# SystemMemory.net
KiCad netlist of a schematic drawn in Altium Designer
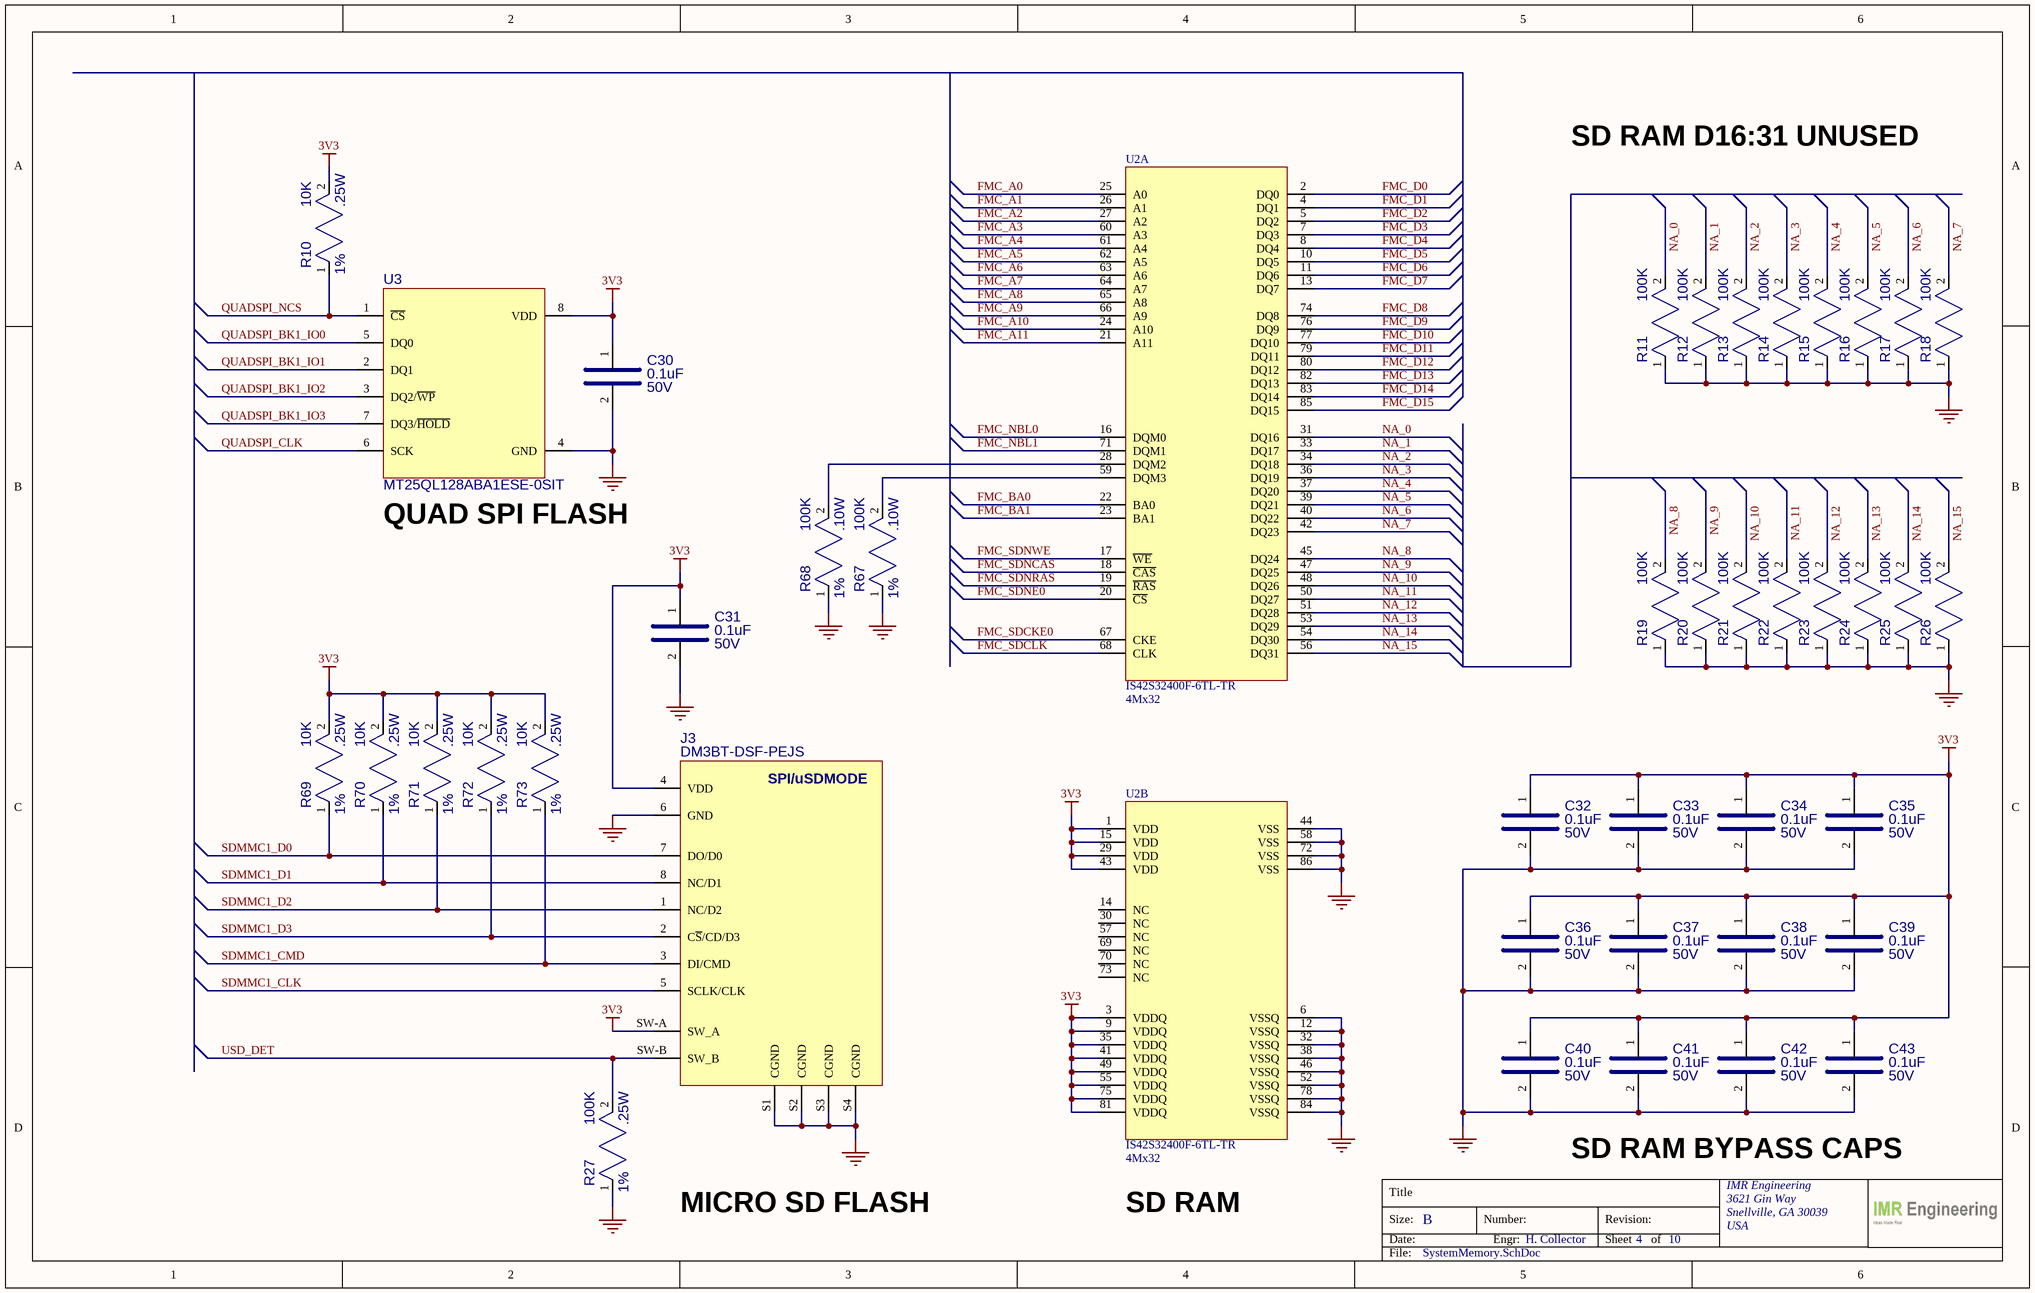
[diagram p0: SystemMemory.SchDoc]

(export (version "E")
  (design (tool "Eeschema 10.0.6"))
  (components
    (comp (ref "C30")
      (value "0.1uF")
      (footprint "CAP_0805")
      (description "CAP CER 0.1UF 50V X7R 0805")
      (fields (field (name "MFG") "AVX") (field (name "TOLERANCE") "10%") (field (name "VOLTAGE") "50V"))
      (libsource (lib "IMR_Lib") (part "CAP_0.1UF_50V_0805"))
    )
    (comp (ref "C31")
      (value "0.1uF")
      (footprint "CAP_0805")
      (description "CAP CER 0.1UF 50V X7R 0805")
      (fields (field (name "MFG") "AVX") (field (name "TOLERANCE") "10%") (field (name "VOLTAGE") "50V"))
      (libsource (lib "IMR_Lib") (part "CAP_0.1UF_50V_0805"))
    )
    (comp (ref "C32")
      (value "0.1uF")
      (footprint "CAP_0603")
      (description "CAP CER 0.1UF 50V X7R 0603")
      (fields (field (name "MFG") "Yageo") (field (name "TOLERANCE") "10%") (field (name "VOLTAGE") "50V"))
      (libsource (lib "IMR_Lib") (part "CAP_0.1UF_50V_0603"))
    )
    (comp (ref "C33")
      (value "0.1uF")
      (footprint "CAP_0603")
      (description "CAP CER 0.1UF 50V X7R 0603")
      (fields (field (name "MFG") "Yageo") (field (name "TOLERANCE") "10%") (field (name "VOLTAGE") "50V"))
      (libsource (lib "IMR_Lib") (part "CAP_0.1UF_50V_0603"))
    )
    (comp (ref "C34")
      (value "0.1uF")
      (footprint "CAP_0603")
      (description "CAP CER 0.1UF 50V X7R 0603")
      (fields (field (name "MFG") "Yageo") (field (name "TOLERANCE") "10%") (field (name "VOLTAGE") "50V"))
      (libsource (lib "IMR_Lib") (part "CAP_0.1UF_50V_0603"))
    )
    (comp (ref "C35")
      (value "0.1uF")
      (footprint "CAP_0603")
      (description "CAP CER 0.1UF 50V X7R 0603")
      (fields (field (name "MFG") "Yageo") (field (name "TOLERANCE") "10%") (field (name "VOLTAGE") "50V"))
      (libsource (lib "IMR_Lib") (part "CAP_0.1UF_50V_0603"))
    )
    (comp (ref "C36")
      (value "0.1uF")
      (footprint "CAP_0603")
      (description "CAP CER 0.1UF 50V X7R 0603")
      (fields (field (name "MFG") "Yageo") (field (name "TOLERANCE") "10%") (field (name "VOLTAGE") "50V"))
      (libsource (lib "IMR_Lib") (part "CAP_0.1UF_50V_0603"))
    )
    (comp (ref "C37")
      (value "0.1uF")
      (footprint "CAP_0603")
      (description "CAP CER 0.1UF 50V X7R 0603")
      (fields (field (name "MFG") "Yageo") (field (name "TOLERANCE") "10%") (field (name "VOLTAGE") "50V"))
      (libsource (lib "IMR_Lib") (part "CAP_0.1UF_50V_0603"))
    )
    (comp (ref "C38")
      (value "0.1uF")
      (footprint "CAP_0603")
      (description "CAP CER 0.1UF 50V X7R 0603")
      (fields (field (name "MFG") "Yageo") (field (name "TOLERANCE") "10%") (field (name "VOLTAGE") "50V"))
      (libsource (lib "IMR_Lib") (part "CAP_0.1UF_50V_0603"))
    )
    (comp (ref "C39")
      (value "0.1uF")
      (footprint "CAP_0603")
      (description "CAP CER 0.1UF 50V X7R 0603")
      (fields (field (name "MFG") "Yageo") (field (name "TOLERANCE") "10%") (field (name "VOLTAGE") "50V"))
      (libsource (lib "IMR_Lib") (part "CAP_0.1UF_50V_0603"))
    )
    (comp (ref "C40")
      (value "0.1uF")
      (footprint "CAP_0603")
      (description "CAP CER 0.1UF 50V X7R 0603")
      (fields (field (name "MFG") "Yageo") (field (name "TOLERANCE") "10%") (field (name "VOLTAGE") "50V"))
      (libsource (lib "IMR_Lib") (part "CAP_0.1UF_50V_0603"))
    )
    (comp (ref "C41")
      (value "0.1uF")
      (footprint "CAP_0603")
      (description "CAP CER 0.1UF 50V X7R 0603")
      (fields (field (name "MFG") "Yageo") (field (name "TOLERANCE") "10%") (field (name "VOLTAGE") "50V"))
      (libsource (lib "IMR_Lib") (part "CAP_0.1UF_50V_0603"))
    )
    (comp (ref "C42")
      (value "0.1uF")
      (footprint "CAP_0603")
      (description "CAP CER 0.1UF 50V X7R 0603")
      (fields (field (name "MFG") "Yageo") (field (name "TOLERANCE") "10%") (field (name "VOLTAGE") "50V"))
      (libsource (lib "IMR_Lib") (part "CAP_0.1UF_50V_0603"))
    )
    (comp (ref "C43")
      (value "0.1uF")
      (footprint "CAP_0603")
      (description "CAP CER 0.1UF 50V X7R 0603")
      (fields (field (name "MFG") "Yageo") (field (name "TOLERANCE") "10%") (field (name "VOLTAGE") "50V"))
      (libsource (lib "IMR_Lib") (part "CAP_0.1UF_50V_0603"))
    )
    (comp (ref "J3")
      (value "DM3BT-DSF-PEJS")
      (footprint "HRS_DM3BT-DSF-PEJS")
      (description "CONN MICRO SD CARD PUSH-PUSH R/A")
      (fields (field (name "MFG") "Hirose Electric Co Ltd"))
      (libsource (lib "IMR_Lib") (part "CONN_HIROSE_DM3BT-DSF-PEJS"))
    )
    (comp (ref "R10")
      (value "10K")
      (footprint "RES_0805")
      (description "RES SMD 10K OHM 1% 1/4W 0805")
      (fields
        (field (name "MFG") "KOA Speer Electronics, Inc.")
        (field (name "TOLERANCE") "1%")
        (field (name "POWER") ".25W")
        (field (name "Comment") "SG73S2ATTD1002F")
      )
      (libsource (lib "IMR_Lib") (part "RES_10K_0805_1/4W_1%"))
    )
    (comp (ref "R11")
      (value "100K")
      (footprint "RES_0603")
      (description "RES SMD 100K OHM 1% 1/10W 0603")
      (fields (field (name "MFG") "Yageo") (field (name "TOLERANCE") "1%"))
      (libsource (lib "IMR_Lib") (part "RES_100K_0603_1/10W_1%"))
    )
    (comp (ref "R12")
      (value "100K")
      (footprint "RES_0603")
      (description "RES SMD 100K OHM 1% 1/10W 0603")
      (fields (field (name "MFG") "Yageo") (field (name "TOLERANCE") "1%"))
      (libsource (lib "IMR_Lib") (part "RES_100K_0603_1/10W_1%"))
    )
    (comp (ref "R13")
      (value "100K")
      (footprint "RES_0603")
      (description "RES SMD 100K OHM 1% 1/10W 0603")
      (fields (field (name "MFG") "Yageo") (field (name "TOLERANCE") "1%"))
      (libsource (lib "IMR_Lib") (part "RES_100K_0603_1/10W_1%"))
    )
    (comp (ref "R14")
      (value "100K")
      (footprint "RES_0603")
      (description "RES SMD 100K OHM 1% 1/10W 0603")
      (fields (field (name "MFG") "Yageo") (field (name "TOLERANCE") "1%"))
      (libsource (lib "IMR_Lib") (part "RES_100K_0603_1/10W_1%"))
    )
    (comp (ref "R15")
      (value "100K")
      (footprint "RES_0603")
      (description "RES SMD 100K OHM 1% 1/10W 0603")
      (fields (field (name "MFG") "Yageo") (field (name "TOLERANCE") "1%"))
      (libsource (lib "IMR_Lib") (part "RES_100K_0603_1/10W_1%"))
    )
    (comp (ref "R16")
      (value "100K")
      (footprint "RES_0603")
      (description "RES SMD 100K OHM 1% 1/10W 0603")
      (fields (field (name "MFG") "Yageo") (field (name "TOLERANCE") "1%"))
      (libsource (lib "IMR_Lib") (part "RES_100K_0603_1/10W_1%"))
    )
    (comp (ref "R17")
      (value "100K")
      (footprint "RES_0603")
      (description "RES SMD 100K OHM 1% 1/10W 0603")
      (fields (field (name "MFG") "Yageo") (field (name "TOLERANCE") "1%"))
      (libsource (lib "IMR_Lib") (part "RES_100K_0603_1/10W_1%"))
    )
    (comp (ref "R18")
      (value "100K")
      (footprint "RES_0603")
      (description "RES SMD 100K OHM 1% 1/10W 0603")
      (fields (field (name "MFG") "Yageo") (field (name "TOLERANCE") "1%"))
      (libsource (lib "IMR_Lib") (part "RES_100K_0603_1/10W_1%"))
    )
    (comp (ref "R19")
      (value "100K")
      (footprint "RES_0603")
      (description "RES SMD 100K OHM 1% 1/10W 0603")
      (fields (field (name "MFG") "Yageo") (field (name "TOLERANCE") "1%"))
      (libsource (lib "IMR_Lib") (part "RES_100K_0603_1/10W_1%"))
    )
    (comp (ref "R20")
      (value "100K")
      (footprint "RES_0603")
      (description "RES SMD 100K OHM 1% 1/10W 0603")
      (fields (field (name "MFG") "Yageo") (field (name "TOLERANCE") "1%"))
      (libsource (lib "IMR_Lib") (part "RES_100K_0603_1/10W_1%"))
    )
    (comp (ref "R21")
      (value "100K")
      (footprint "RES_0603")
      (description "RES SMD 100K OHM 1% 1/10W 0603")
      (fields (field (name "MFG") "Yageo") (field (name "TOLERANCE") "1%"))
      (libsource (lib "IMR_Lib") (part "RES_100K_0603_1/10W_1%"))
    )
    (comp (ref "R22")
      (value "100K")
      (footprint "RES_0603")
      (description "RES SMD 100K OHM 1% 1/10W 0603")
      (fields (field (name "MFG") "Yageo") (field (name "TOLERANCE") "1%"))
      (libsource (lib "IMR_Lib") (part "RES_100K_0603_1/10W_1%"))
    )
    (comp (ref "R23")
      (value "100K")
      (footprint "RES_0603")
      (description "RES SMD 100K OHM 1% 1/10W 0603")
      (fields (field (name "MFG") "Yageo") (field (name "TOLERANCE") "1%"))
      (libsource (lib "IMR_Lib") (part "RES_100K_0603_1/10W_1%"))
    )
    (comp (ref "R24")
      (value "100K")
      (footprint "RES_0603")
      (description "RES SMD 100K OHM 1% 1/10W 0603")
      (fields (field (name "MFG") "Yageo") (field (name "TOLERANCE") "1%"))
      (libsource (lib "IMR_Lib") (part "RES_100K_0603_1/10W_1%"))
    )
    (comp (ref "R25")
      (value "100K")
      (footprint "RES_0603")
      (description "RES SMD 100K OHM 1% 1/10W 0603")
      (fields (field (name "MFG") "Yageo") (field (name "TOLERANCE") "1%"))
      (libsource (lib "IMR_Lib") (part "RES_100K_0603_1/10W_1%"))
    )
    (comp (ref "R26")
      (value "100K")
      (footprint "RES_0603")
      (description "RES SMD 100K OHM 1% 1/10W 0603")
      (fields (field (name "MFG") "Yageo") (field (name "TOLERANCE") "1%"))
      (libsource (lib "IMR_Lib") (part "RES_100K_0603_1/10W_1%"))
    )
    (comp (ref "R27")
      (value "100K")
      (footprint "PMG_RES_0805")
      (description "RES SMD 100K OHM 1% 1/4W 0805")
      (fields
        (field (name "MFG") "KOA Speer Electronics, Inc.")
        (field (name "TOLERANCE") "1%")
        (field (name "POWER") ".25W")
        (field (name "Comment") "RK73H2ATTD1003F")
      )
      (libsource (lib "IMR_Lib") (part "RES_100K_0805_1/4W_1%"))
    )
    (comp (ref "R67")
      (value "100K")
      (footprint "RES_0603")
      (description "RES SMD 100K OHM 1% 1/10W 0603")
      (fields
        (field (name "MFG") "Yageo")
        (field (name "TOLERANCE") "1%")
        (field (name "POWER") ".10W")
        (field (name "Comment") "RC0603FR-07100KL")
      )
      (libsource (lib "IMR_Lib") (part "RES_100K_0603_1/10W_1%"))
    )
    (comp (ref "R68")
      (value "100K")
      (footprint "RES_0603")
      (description "RES SMD 100K OHM 1% 1/10W 0603")
      (fields
        (field (name "MFG") "Yageo")
        (field (name "TOLERANCE") "1%")
        (field (name "POWER") ".10W")
        (field (name "Comment") "RC0603FR-07100KL")
      )
      (libsource (lib "IMR_Lib") (part "RES_100K_0603_1/10W_1%"))
    )
    (comp (ref "R69")
      (value "10K")
      (footprint "RES_0805")
      (description "RES SMD 10K OHM 1% 1/4W 0805")
      (fields
        (field (name "MFG") "KOA Speer Electronics, Inc.")
        (field (name "TOLERANCE") "1%")
        (field (name "POWER") ".25W")
        (field (name "Comment") "SG73S2ATTD1002F")
      )
      (libsource (lib "IMR_Lib") (part "RES_10K_0805_1/4W_1%"))
    )
    (comp (ref "R70")
      (value "10K")
      (footprint "RES_0805")
      (description "RES SMD 10K OHM 1% 1/4W 0805")
      (fields
        (field (name "MFG") "KOA Speer Electronics, Inc.")
        (field (name "TOLERANCE") "1%")
        (field (name "POWER") ".25W")
        (field (name "Comment") "SG73S2ATTD1002F")
      )
      (libsource (lib "IMR_Lib") (part "RES_10K_0805_1/4W_1%"))
    )
    (comp (ref "R71")
      (value "10K")
      (footprint "RES_0805")
      (description "RES SMD 10K OHM 1% 1/4W 0805")
      (fields
        (field (name "MFG") "KOA Speer Electronics, Inc.")
        (field (name "TOLERANCE") "1%")
        (field (name "POWER") ".25W")
        (field (name "Comment") "SG73S2ATTD1002F")
      )
      (libsource (lib "IMR_Lib") (part "RES_10K_0805_1/4W_1%"))
    )
    (comp (ref "R72")
      (value "10K")
      (footprint "RES_0805")
      (description "RES SMD 10K OHM 1% 1/4W 0805")
      (fields
        (field (name "MFG") "KOA Speer Electronics, Inc.")
        (field (name "TOLERANCE") "1%")
        (field (name "POWER") ".25W")
        (field (name "Comment") "SG73S2ATTD1002F")
      )
      (libsource (lib "IMR_Lib") (part "RES_10K_0805_1/4W_1%"))
    )
    (comp (ref "R73")
      (value "10K")
      (footprint "RES_0805")
      (description "RES SMD 10K OHM 1% 1/4W 0805")
      (fields
        (field (name "MFG") "KOA Speer Electronics, Inc.")
        (field (name "TOLERANCE") "1%")
        (field (name "POWER") ".25W")
        (field (name "Comment") "SG73S2ATTD1002F")
      )
      (libsource (lib "IMR_Lib") (part "RES_10K_0805_1/4W_1%"))
    )
    (comp (ref "U2")
      (value "IS42S32400F-6TL-TR")
      (footprint "86TSOPII")
      (description "IC DRAM 128M PARALLEL 86TSOP II")
      (fields
        (field (name "MFG") "ISSI, Integrated Silicon Solution Inc")
        (field (name "ALTIUM_VALUE") "4Mx32")
      )
      (libsource (lib "IMR_Lib") (part "IC_ IS42S32400F-6TL"))
    )
    (comp (ref "U3")
      (value "MT25QL128ABA1ESE-0SIT")
      (footprint "SO8W")
      (description "IC FLASH 128M SPI 133MHZ 8SOP2")
      (fields (field (name "MFG") "Micron Technology Inc."))
      (libsource (lib "IMR_Lib") (part "IC_MT25QL128ABA1ESE-0SIT"))
    )
  )
  (nets
    (net (code "1") (name "/FMC_A0") (class "Default")
      (node (ref "U2") (pin "25") (pinfunction "A0_25") (pintype "passive"))
    )
    (net (code "2") (name "/FMC_A1") (class "Default")
      (node (ref "U2") (pin "26") (pinfunction "A1_26") (pintype "passive"))
    )
    (net (code "3") (name "/FMC_A2") (class "Default")
      (node (ref "U2") (pin "27") (pinfunction "A2_27") (pintype "passive"))
    )
    (net (code "4") (name "/FMC_A3") (class "Default")
      (node (ref "U2") (pin "60") (pinfunction "A3_60") (pintype "passive"))
    )
    (net (code "5") (name "/FMC_A4") (class "Default")
      (node (ref "U2") (pin "61") (pinfunction "A4_61") (pintype "passive"))
    )
    (net (code "6") (name "/FMC_A5") (class "Default")
      (node (ref "U2") (pin "62") (pinfunction "A5_62") (pintype "passive"))
    )
    (net (code "7") (name "/FMC_A6") (class "Default")
      (node (ref "U2") (pin "63") (pinfunction "A6_63") (pintype "passive"))
    )
    (net (code "8") (name "/FMC_A7") (class "Default")
      (node (ref "U2") (pin "64") (pinfunction "A7_64") (pintype "passive"))
    )
    (net (code "9") (name "/FMC_A8") (class "Default")
      (node (ref "U2") (pin "65") (pinfunction "A8_65") (pintype "passive"))
    )
    (net (code "10") (name "/FMC_A9") (class "Default")
      (node (ref "U2") (pin "66") (pinfunction "A9_66") (pintype "passive"))
    )
    (net (code "11") (name "/FMC_A10") (class "Default")
      (node (ref "U2") (pin "24") (pinfunction "A10_24") (pintype "passive"))
    )
    (net (code "12") (name "/FMC_A11") (class "Default")
      (node (ref "U2") (pin "21") (pinfunction "A11_21") (pintype "passive"))
    )
    (net (code "13") (name "/FMC_BA0") (class "Default")
      (node (ref "U2") (pin "22") (pinfunction "BA0_22") (pintype "passive"))
    )
    (net (code "14") (name "/FMC_BA1") (class "Default")
      (node (ref "U2") (pin "23") (pinfunction "BA1_23") (pintype "passive"))
    )
    (net (code "15") (name "/FMC_D0") (class "Default")
      (node (ref "U2") (pin "2") (pinfunction "DQ0_2") (pintype "passive"))
    )
    (net (code "16") (name "/FMC_D1") (class "Default")
      (node (ref "U2") (pin "4") (pinfunction "DQ1_4") (pintype "passive"))
    )
    (net (code "17") (name "/FMC_D2") (class "Default")
      (node (ref "U2") (pin "5") (pinfunction "DQ2_5") (pintype "passive"))
    )
    (net (code "18") (name "/FMC_D3") (class "Default")
      (node (ref "U2") (pin "7") (pinfunction "DQ3_7") (pintype "passive"))
    )
    (net (code "19") (name "/FMC_D4") (class "Default")
      (node (ref "U2") (pin "8") (pinfunction "DQ4_8") (pintype "passive"))
    )
    (net (code "20") (name "/FMC_D5") (class "Default")
      (node (ref "U2") (pin "10") (pinfunction "DQ5_10") (pintype "passive"))
    )
    (net (code "21") (name "/FMC_D6") (class "Default")
      (node (ref "U2") (pin "11") (pinfunction "DQ6_11") (pintype "passive"))
    )
    (net (code "22") (name "/FMC_D7") (class "Default")
      (node (ref "U2") (pin "13") (pinfunction "DQ7_13") (pintype "passive"))
    )
    (net (code "23") (name "/FMC_D8") (class "Default")
      (node (ref "U2") (pin "74") (pinfunction "DQ8_74") (pintype "passive"))
    )
    (net (code "24") (name "/FMC_D9") (class "Default")
      (node (ref "U2") (pin "76") (pinfunction "DQ9_76") (pintype "passive"))
    )
    (net (code "25") (name "/FMC_D10") (class "Default")
      (node (ref "U2") (pin "77") (pinfunction "DQ10_77") (pintype "passive"))
    )
    (net (code "26") (name "/FMC_D11") (class "Default")
      (node (ref "U2") (pin "79") (pinfunction "DQ11_79") (pintype "passive"))
    )
    (net (code "27") (name "/FMC_D12") (class "Default")
      (node (ref "U2") (pin "80") (pinfunction "DQ12_80") (pintype "passive"))
    )
    (net (code "28") (name "/FMC_D13") (class "Default")
      (node (ref "U2") (pin "82") (pinfunction "DQ13_82") (pintype "passive"))
    )
    (net (code "29") (name "/FMC_D14") (class "Default")
      (node (ref "U2") (pin "83") (pinfunction "DQ14_83") (pintype "passive"))
    )
    (net (code "30") (name "/FMC_D15") (class "Default")
      (node (ref "U2") (pin "85") (pinfunction "DQ15_85") (pintype "passive"))
    )
    (net (code "31") (name "/FMC_NBL0") (class "Default")
      (node (ref "U2") (pin "16") (pinfunction "DQM0_16") (pintype "passive"))
    )
    (net (code "32") (name "/FMC_NBL1") (class "Default")
      (node (ref "U2") (pin "71") (pinfunction "DQM1_71") (pintype "passive"))
    )
    (net (code "33") (name "/FMC_SDCKE0") (class "Default")
      (node (ref "U2") (pin "67") (pinfunction "CKE_67") (pintype "passive"))
    )
    (net (code "34") (name "/FMC_SDCLK") (class "Default")
      (node (ref "U2") (pin "68") (pinfunction "CLK_68") (pintype "passive"))
    )
    (net (code "35") (name "/FMC_SDNCAS") (class "Default")
      (node (ref "U2") (pin "18") (pinfunction "CAS_18") (pintype "passive"))
    )
    (net (code "36") (name "/FMC_SDNE0") (class "Default")
      (node (ref "U2") (pin "20") (pinfunction "CS_20") (pintype "passive"))
    )
    (net (code "37") (name "/FMC_SDNRAS") (class "Default")
      (node (ref "U2") (pin "19") (pinfunction "RAS_19") (pintype "passive"))
    )
    (net (code "38") (name "/FMC_SDNWE") (class "Default")
      (node (ref "U2") (pin "17") (pinfunction "WE_17") (pintype "passive"))
    )
    (net (code "39") (name "/NA_0") (class "Default")
      (node (ref "R11") (pin "2") (pinfunction "2_2") (pintype "passive"))
      (node (ref "U2") (pin "31") (pinfunction "DQ16_31") (pintype "passive"))
    )
    (net (code "40") (name "/NA_1") (class "Default")
      (node (ref "R12") (pin "2") (pinfunction "2_2") (pintype "passive"))
      (node (ref "U2") (pin "33") (pinfunction "DQ17_33") (pintype "passive"))
    )
    (net (code "41") (name "/NA_2") (class "Default")
      (node (ref "R13") (pin "2") (pinfunction "2_2") (pintype "passive"))
      (node (ref "U2") (pin "34") (pinfunction "DQ18_34") (pintype "passive"))
    )
    (net (code "42") (name "/NA_3") (class "Default")
      (node (ref "R14") (pin "2") (pinfunction "2_2") (pintype "passive"))
      (node (ref "U2") (pin "36") (pinfunction "DQ19_36") (pintype "passive"))
    )
    (net (code "43") (name "/NA_4") (class "Default")
      (node (ref "R15") (pin "2") (pinfunction "2_2") (pintype "passive"))
      (node (ref "U2") (pin "37") (pinfunction "DQ20_37") (pintype "passive"))
    )
    (net (code "44") (name "/NA_5") (class "Default")
      (node (ref "R16") (pin "2") (pinfunction "2_2") (pintype "passive"))
      (node (ref "U2") (pin "39") (pinfunction "DQ21_39") (pintype "passive"))
    )
    (net (code "45") (name "/NA_6") (class "Default")
      (node (ref "R17") (pin "2") (pinfunction "2_2") (pintype "passive"))
      (node (ref "U2") (pin "40") (pinfunction "DQ22_40") (pintype "passive"))
    )
    (net (code "46") (name "/NA_7") (class "Default")
      (node (ref "R18") (pin "2") (pinfunction "2_2") (pintype "passive"))
      (node (ref "U2") (pin "42") (pinfunction "DQ23_42") (pintype "passive"))
    )
    (net (code "47") (name "/NA_8") (class "Default")
      (node (ref "R19") (pin "2") (pinfunction "2_2") (pintype "passive"))
      (node (ref "U2") (pin "45") (pinfunction "DQ24_45") (pintype "passive"))
    )
    (net (code "48") (name "/NA_9") (class "Default")
      (node (ref "R20") (pin "2") (pinfunction "2_2") (pintype "passive"))
      (node (ref "U2") (pin "47") (pinfunction "DQ25_47") (pintype "passive"))
    )
    (net (code "49") (name "/NA_10") (class "Default")
      (node (ref "R21") (pin "2") (pinfunction "2_2") (pintype "passive"))
      (node (ref "U2") (pin "48") (pinfunction "DQ26_48") (pintype "passive"))
    )
    (net (code "50") (name "/NA_11") (class "Default")
      (node (ref "R22") (pin "2") (pinfunction "2_2") (pintype "passive"))
      (node (ref "U2") (pin "50") (pinfunction "DQ27_50") (pintype "passive"))
    )
    (net (code "51") (name "/NA_12") (class "Default")
      (node (ref "R23") (pin "2") (pinfunction "2_2") (pintype "passive"))
      (node (ref "U2") (pin "51") (pinfunction "DQ28_51") (pintype "passive"))
    )
    (net (code "52") (name "/NA_13") (class "Default")
      (node (ref "R24") (pin "2") (pinfunction "2_2") (pintype "passive"))
      (node (ref "U2") (pin "53") (pinfunction "DQ29_53") (pintype "passive"))
    )
    (net (code "53") (name "/NA_14") (class "Default")
      (node (ref "R25") (pin "2") (pinfunction "2_2") (pintype "passive"))
      (node (ref "U2") (pin "54") (pinfunction "DQ30_54") (pintype "passive"))
    )
    (net (code "54") (name "/NA_15") (class "Default")
      (node (ref "R26") (pin "2") (pinfunction "2_2") (pintype "passive"))
      (node (ref "U2") (pin "56") (pinfunction "DQ31_56") (pintype "passive"))
    )
    (net (code "55") (name "/QUADSPI_BK1_IO0") (class "Default")
      (node (ref "U3") (pin "5") (pinfunction "DQ0_5") (pintype "passive"))
    )
    (net (code "56") (name "/QUADSPI_BK1_IO1") (class "Default")
      (node (ref "U3") (pin "2") (pinfunction "DQ1_2") (pintype "passive"))
    )
    (net (code "57") (name "/QUADSPI_BK1_IO2") (class "Default")
      (node (ref "U3") (pin "3") (pinfunction "DQ2/~{WP}_3") (pintype "passive"))
    )
    (net (code "58") (name "/QUADSPI_BK1_IO3") (class "Default")
      (node (ref "U3") (pin "7") (pinfunction "DQ3/~{HOLD}_7") (pintype "passive"))
    )
    (net (code "59") (name "/QUADSPI_CLK") (class "Default")
      (node (ref "U3") (pin "6") (pinfunction "SCK_6") (pintype "passive"))
    )
    (net (code "60") (name "/QUADSPI_NCS") (class "Default")
      (node (ref "R10") (pin "1") (pinfunction "1_1") (pintype "passive"))
      (node (ref "U3") (pin "1") (pinfunction "CS_1") (pintype "passive"))
    )
    (net (code "61") (name "/SDMMC1_CLK") (class "Default")
      (node (ref "J3") (pin "5") (pinfunction "SCLK/CLK_5") (pintype "passive"))
    )
    (net (code "62") (name "/SDMMC1_CMD") (class "Default")
      (node (ref "J3") (pin "3") (pinfunction "DI/CMD_3") (pintype "passive"))
      (node (ref "R73") (pin "1") (pinfunction "1_1") (pintype "passive"))
    )
    (net (code "63") (name "/SDMMC1_D0") (class "Default")
      (node (ref "J3") (pin "7") (pinfunction "DO/D0_7") (pintype "passive"))
      (node (ref "R69") (pin "1") (pinfunction "1_1") (pintype "passive"))
    )
    (net (code "64") (name "/SDMMC1_D1") (class "Default")
      (node (ref "J3") (pin "8") (pinfunction "NC/D1_8") (pintype "passive"))
      (node (ref "R70") (pin "1") (pinfunction "1_1") (pintype "passive"))
    )
    (net (code "65") (name "/SDMMC1_D2") (class "Default")
      (node (ref "J3") (pin "1") (pinfunction "NC/D2_1") (pintype "passive"))
      (node (ref "R71") (pin "1") (pinfunction "1_1") (pintype "passive"))
    )
    (net (code "66") (name "/SDMMC1_D3") (class "Default")
      (node (ref "J3") (pin "2") (pinfunction "C~{S}/CD/D3_2") (pintype "passive"))
      (node (ref "R72") (pin "1") (pinfunction "1_1") (pintype "passive"))
    )
    (net (code "67") (name "/USD_DET") (class "Default")
      (node (ref "J3") (pin "SW-B") (pinfunction "SW_B_SW-B") (pintype "passive"))
      (node (ref "R27") (pin "2") (pinfunction "2_2") (pintype "passive"))
    )
    (net (code "68") (name "3V3") (class "Default")
      (node (ref "C30") (pin "1") (pinfunction "1_1") (pintype "passive"))
      (node (ref "C31") (pin "1") (pinfunction "1_1") (pintype "passive"))
      (node (ref "C32") (pin "1") (pinfunction "1_1") (pintype "passive"))
      (node (ref "C33") (pin "1") (pinfunction "1_1") (pintype "passive"))
      (node (ref "C34") (pin "1") (pinfunction "1_1") (pintype "passive"))
      (node (ref "C35") (pin "1") (pinfunction "1_1") (pintype "passive"))
      (node (ref "C36") (pin "1") (pinfunction "1_1") (pintype "passive"))
      (node (ref "C37") (pin "1") (pinfunction "1_1") (pintype "passive"))
      (node (ref "C38") (pin "1") (pinfunction "1_1") (pintype "passive"))
      (node (ref "C39") (pin "1") (pinfunction "1_1") (pintype "passive"))
      (node (ref "C40") (pin "1") (pinfunction "1_1") (pintype "passive"))
      (node (ref "C41") (pin "1") (pinfunction "1_1") (pintype "passive"))
      (node (ref "C42") (pin "1") (pinfunction "1_1") (pintype "passive"))
      (node (ref "C43") (pin "1") (pinfunction "1_1") (pintype "passive"))
      (node (ref "J3") (pin "4") (pinfunction "VDD_4") (pintype "passive"))
      (node (ref "J3") (pin "SW-A") (pinfunction "SW_A_SW-A") (pintype "passive"))
      (node (ref "R10") (pin "2") (pinfunction "2_2") (pintype "passive"))
      (node (ref "R69") (pin "2") (pinfunction "2_2") (pintype "passive"))
      (node (ref "R70") (pin "2") (pinfunction "2_2") (pintype "passive"))
      (node (ref "R71") (pin "2") (pinfunction "2_2") (pintype "passive"))
      (node (ref "R72") (pin "2") (pinfunction "2_2") (pintype "passive"))
      (node (ref "R73") (pin "2") (pinfunction "2_2") (pintype "passive"))
      (node (ref "U2") (pin "1") (pinfunction "VDD_1") (pintype "passive"))
      (node (ref "U2") (pin "15") (pinfunction "VDD_15") (pintype "passive"))
      (node (ref "U2") (pin "29") (pinfunction "VDD_29") (pintype "passive"))
      (node (ref "U2") (pin "3") (pinfunction "VDDQ_3") (pintype "passive"))
      (node (ref "U2") (pin "35") (pinfunction "VDDQ_35") (pintype "passive"))
      (node (ref "U2") (pin "41") (pinfunction "VDDQ_41") (pintype "passive"))
      (node (ref "U2") (pin "43") (pinfunction "VDD_43") (pintype "passive"))
      (node (ref "U2") (pin "49") (pinfunction "VDDQ_49") (pintype "passive"))
      (node (ref "U2") (pin "55") (pinfunction "VDDQ_55") (pintype "passive"))
      (node (ref "U2") (pin "75") (pinfunction "VDDQ_75") (pintype "passive"))
      (node (ref "U2") (pin "81") (pinfunction "VDDQ_81") (pintype "passive"))
      (node (ref "U2") (pin "9") (pinfunction "VDDQ_9") (pintype "passive"))
      (node (ref "U3") (pin "8") (pinfunction "VDD_8") (pintype "passive"))
    )
    (net (code "69") (name "GND") (class "Default")
      (node (ref "C30") (pin "2") (pinfunction "2_2") (pintype "passive"))
      (node (ref "C31") (pin "2") (pinfunction "2_2") (pintype "passive"))
      (node (ref "C32") (pin "2") (pinfunction "2_2") (pintype "passive"))
      (node (ref "C33") (pin "2") (pinfunction "2_2") (pintype "passive"))
      (node (ref "C34") (pin "2") (pinfunction "2_2") (pintype "passive"))
      (node (ref "C35") (pin "2") (pinfunction "2_2") (pintype "passive"))
      (node (ref "C36") (pin "2") (pinfunction "2_2") (pintype "passive"))
      (node (ref "C37") (pin "2") (pinfunction "2_2") (pintype "passive"))
      (node (ref "C38") (pin "2") (pinfunction "2_2") (pintype "passive"))
      (node (ref "C39") (pin "2") (pinfunction "2_2") (pintype "passive"))
      (node (ref "C40") (pin "2") (pinfunction "2_2") (pintype "passive"))
      (node (ref "C41") (pin "2") (pinfunction "2_2") (pintype "passive"))
      (node (ref "C42") (pin "2") (pinfunction "2_2") (pintype "passive"))
      (node (ref "C43") (pin "2") (pinfunction "2_2") (pintype "passive"))
      (node (ref "J3") (pin "6") (pinfunction "GND_6") (pintype "passive"))
      (node (ref "J3") (pin "S1") (pinfunction "CGND_S1") (pintype "passive"))
      (node (ref "J3") (pin "S2") (pinfunction "CGND_S2") (pintype "passive"))
      (node (ref "J3") (pin "S3") (pinfunction "CGND_S3") (pintype "passive"))
      (node (ref "J3") (pin "S4") (pinfunction "CGND_S4") (pintype "passive"))
      (node (ref "R11") (pin "1") (pinfunction "1_1") (pintype "passive"))
      (node (ref "R12") (pin "1") (pinfunction "1_1") (pintype "passive"))
      (node (ref "R13") (pin "1") (pinfunction "1_1") (pintype "passive"))
      (node (ref "R14") (pin "1") (pinfunction "1_1") (pintype "passive"))
      (node (ref "R15") (pin "1") (pinfunction "1_1") (pintype "passive"))
      (node (ref "R16") (pin "1") (pinfunction "1_1") (pintype "passive"))
      (node (ref "R17") (pin "1") (pinfunction "1_1") (pintype "passive"))
      (node (ref "R18") (pin "1") (pinfunction "1_1") (pintype "passive"))
      (node (ref "R19") (pin "1") (pinfunction "1_1") (pintype "passive"))
      (node (ref "R20") (pin "1") (pinfunction "1_1") (pintype "passive"))
      (node (ref "R21") (pin "1") (pinfunction "1_1") (pintype "passive"))
      (node (ref "R22") (pin "1") (pinfunction "1_1") (pintype "passive"))
      (node (ref "R23") (pin "1") (pinfunction "1_1") (pintype "passive"))
      (node (ref "R24") (pin "1") (pinfunction "1_1") (pintype "passive"))
      (node (ref "R25") (pin "1") (pinfunction "1_1") (pintype "passive"))
      (node (ref "R26") (pin "1") (pinfunction "1_1") (pintype "passive"))
      (node (ref "R27") (pin "1") (pinfunction "1_1") (pintype "passive"))
      (node (ref "R67") (pin "1") (pinfunction "1_1") (pintype "passive"))
      (node (ref "R68") (pin "1") (pinfunction "1_1") (pintype "passive"))
      (node (ref "U2") (pin "12") (pinfunction "VSSQ_12") (pintype "passive"))
      (node (ref "U2") (pin "32") (pinfunction "VSSQ_32") (pintype "passive"))
      (node (ref "U2") (pin "38") (pinfunction "VSSQ_38") (pintype "passive"))
      (node (ref "U2") (pin "44") (pinfunction "VSS_44") (pintype "passive"))
      (node (ref "U2") (pin "46") (pinfunction "VSSQ_46") (pintype "passive"))
      (node (ref "U2") (pin "52") (pinfunction "VSSQ_52") (pintype "passive"))
      (node (ref "U2") (pin "58") (pinfunction "VSS_58") (pintype "passive"))
      (node (ref "U2") (pin "6") (pinfunction "VSSQ_6") (pintype "passive"))
      (node (ref "U2") (pin "72") (pinfunction "VSS_72") (pintype "passive"))
      (node (ref "U2") (pin "78") (pinfunction "VSSQ_78") (pintype "passive"))
      (node (ref "U2") (pin "84") (pinfunction "VSSQ_84") (pintype "passive"))
      (node (ref "U2") (pin "86") (pinfunction "VSS_86") (pintype "passive"))
      (node (ref "U3") (pin "4") (pinfunction "GND_4") (pintype "passive"))
    )
    (net (code "70") (name "Net-(U2A-DQM2)") (class "Default")
      (node (ref "R68") (pin "2") (pinfunction "2_2") (pintype "passive"))
      (node (ref "U2") (pin "28") (pinfunction "DQM2_28") (pintype "passive"))
    )
    (net (code "71") (name "Net-(U2A-DQM3)") (class "Default")
      (node (ref "R67") (pin "2") (pinfunction "2_2") (pintype "passive"))
      (node (ref "U2") (pin "59") (pinfunction "DQM3_59") (pintype "passive"))
    )
    (net (code "72") (name "unconnected-(U2B-NC-Pad14)") (class "Default")
      (node (ref "U2") (pin "14") (pinfunction "NC_14") (pintype "passive"))
    )
    (net (code "73") (name "unconnected-(U2B-NC-Pad30)") (class "Default")
      (node (ref "U2") (pin "30") (pinfunction "NC_30") (pintype "passive"))
    )
    (net (code "74") (name "unconnected-(U2B-NC-Pad57)") (class "Default")
      (node (ref "U2") (pin "57") (pinfunction "NC_57") (pintype "passive"))
    )
    (net (code "75") (name "unconnected-(U2B-NC-Pad69)") (class "Default")
      (node (ref "U2") (pin "69") (pinfunction "NC_69") (pintype "passive"))
    )
    (net (code "76") (name "unconnected-(U2B-NC-Pad70)") (class "Default")
      (node (ref "U2") (pin "70") (pinfunction "NC_70") (pintype "passive"))
    )
    (net (code "77") (name "unconnected-(U2B-NC-Pad73)") (class "Default")
      (node (ref "U2") (pin "73") (pinfunction "NC_73") (pintype "passive"))
    )
  )
)
